# HP32W_GVSpinout.net
KiCad netlist of a schematic drawn in EAGLE
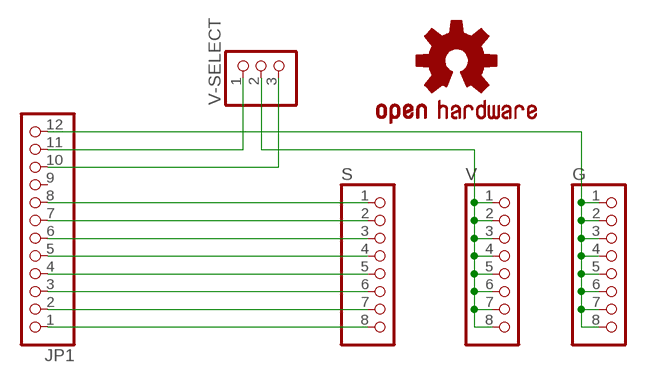
[diagram p0: schematic, sheet 1]

(export (version "E")
  (design (tool "Eeschema 10.0.6"))
  (components
    (comp (ref "G")
      (value "PINHD-1X8BIG")
      (footprint "eagle-import:1X08-BIG")
      (libsource (lib "eagle-import") (part "PINHD-1X8BIG"))
    )
    (comp (ref "JP1")
      (value "PINHD-1X12-CB")
      (footprint "eagle-import:1X12-CB")
      (libsource (lib "eagle-import") (part "PINHD-1X12-CB"))
    )
    (comp (ref "LOGO1")
      (value "OSHW-LOGOS")
      (footprint "eagle-import:OSHW-LOGO-S")
      (libsource (lib "eagle-import") (part "OSHW-LOGOS"))
    )
    (comp (ref "S")
      (value "PINHD-1X8BIG")
      (footprint "eagle-import:1X08-BIG")
      (libsource (lib "eagle-import") (part "PINHD-1X8BIG"))
    )
    (comp (ref "V")
      (value "PINHD-1X8BIG")
      (footprint "eagle-import:1X08-BIG")
      (libsource (lib "eagle-import") (part "PINHD-1X8BIG"))
    )
    (comp (ref "V-SELECT")
      (value "PINHD-1X3")
      (footprint "eagle-import:1X03")
      (libsource (lib "eagle-import") (part "PINHD-1X3"))
    )
  )
  (nets
    (net (code "1") (name "Net-(G-Pad1)") (class "Default")
      (node (ref "G") (pin "1") (pinfunction "1_1") (pintype "passive"))
      (node (ref "G") (pin "2") (pinfunction "2_2") (pintype "passive"))
      (node (ref "G") (pin "3") (pinfunction "3_3") (pintype "passive"))
      (node (ref "G") (pin "4") (pinfunction "4_4") (pintype "passive"))
      (node (ref "G") (pin "5") (pinfunction "5_5") (pintype "passive"))
      (node (ref "G") (pin "6") (pinfunction "6_6") (pintype "passive"))
      (node (ref "G") (pin "7") (pinfunction "7_7") (pintype "passive"))
      (node (ref "G") (pin "8") (pinfunction "8_8") (pintype "passive"))
      (node (ref "JP1") (pin "12") (pinfunction "12_12") (pintype "passive"))
    )
    (net (code "2") (name "Net-(JP1-Pad1)") (class "Default")
      (node (ref "JP1") (pin "1") (pinfunction "1_1") (pintype "passive"))
      (node (ref "S") (pin "8") (pinfunction "8_8") (pintype "passive"))
    )
    (net (code "3") (name "Net-(JP1-Pad2)") (class "Default")
      (node (ref "JP1") (pin "2") (pinfunction "2_2") (pintype "passive"))
      (node (ref "S") (pin "7") (pinfunction "7_7") (pintype "passive"))
    )
    (net (code "4") (name "Net-(JP1-Pad3)") (class "Default")
      (node (ref "JP1") (pin "3") (pinfunction "3_3") (pintype "passive"))
      (node (ref "S") (pin "6") (pinfunction "6_6") (pintype "passive"))
    )
    (net (code "5") (name "Net-(JP1-Pad4)") (class "Default")
      (node (ref "JP1") (pin "4") (pinfunction "4_4") (pintype "passive"))
      (node (ref "S") (pin "5") (pinfunction "5_5") (pintype "passive"))
    )
    (net (code "6") (name "Net-(JP1-Pad5)") (class "Default")
      (node (ref "JP1") (pin "5") (pinfunction "5_5") (pintype "passive"))
      (node (ref "S") (pin "4") (pinfunction "4_4") (pintype "passive"))
    )
    (net (code "7") (name "Net-(JP1-Pad6)") (class "Default")
      (node (ref "JP1") (pin "6") (pinfunction "6_6") (pintype "passive"))
      (node (ref "S") (pin "3") (pinfunction "3_3") (pintype "passive"))
    )
    (net (code "8") (name "Net-(JP1-Pad7)") (class "Default")
      (node (ref "JP1") (pin "7") (pinfunction "7_7") (pintype "passive"))
      (node (ref "S") (pin "2") (pinfunction "2_2") (pintype "passive"))
    )
    (net (code "9") (name "Net-(JP1-Pad8)") (class "Default")
      (node (ref "JP1") (pin "8") (pinfunction "8_8") (pintype "passive"))
      (node (ref "S") (pin "1") (pinfunction "1_1") (pintype "passive"))
    )
    (net (code "10") (name "Net-(JP1-Pad10)") (class "Default")
      (node (ref "JP1") (pin "10") (pinfunction "10_10") (pintype "passive"))
      (node (ref "V-SELECT") (pin "3") (pinfunction "3_3") (pintype "passive"))
    )
    (net (code "11") (name "Net-(JP1-Pad11)") (class "Default")
      (node (ref "JP1") (pin "11") (pinfunction "11_11") (pintype "passive"))
      (node (ref "V-SELECT") (pin "1") (pinfunction "1_1") (pintype "passive"))
    )
    (net (code "12") (name "Net-(V-Pad1)") (class "Default")
      (node (ref "V") (pin "1") (pinfunction "1_1") (pintype "passive"))
      (node (ref "V") (pin "2") (pinfunction "2_2") (pintype "passive"))
      (node (ref "V") (pin "3") (pinfunction "3_3") (pintype "passive"))
      (node (ref "V") (pin "4") (pinfunction "4_4") (pintype "passive"))
      (node (ref "V") (pin "5") (pinfunction "5_5") (pintype "passive"))
      (node (ref "V") (pin "6") (pinfunction "6_6") (pintype "passive"))
      (node (ref "V") (pin "7") (pinfunction "7_7") (pintype "passive"))
      (node (ref "V") (pin "8") (pinfunction "8_8") (pintype "passive"))
      (node (ref "V-SELECT") (pin "2") (pinfunction "2_2") (pintype "passive"))
    )
    (net (code "13") (name "unconnected-(JP1-Pad9)") (class "Default")
      (node (ref "JP1") (pin "9") (pinfunction "9_9") (pintype "passive"))
    )
  )
)
